# IO_Buffer.net
KiCad netlist of a schematic drawn in Altium Designer
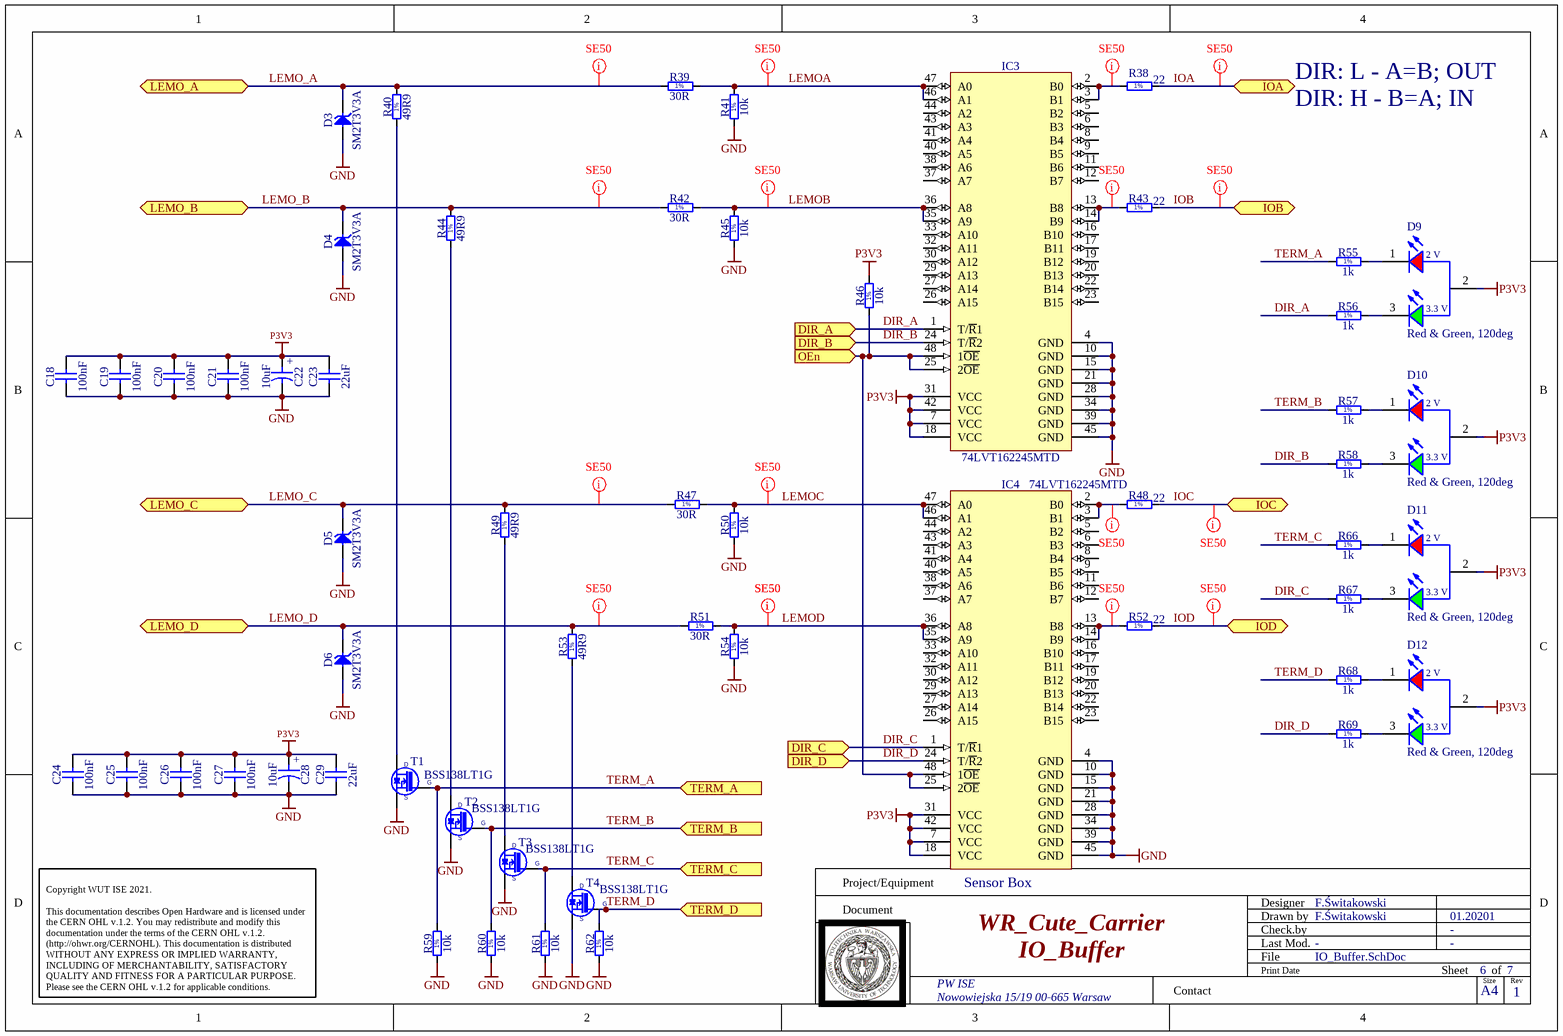
[diagram p0: IO_Buffer.SchDoc]

(export (version "E")
  (design (tool "Eeschema 10.0.6"))
  (components
    (comp (ref "C18")
      (value "100nF")
      (footprint "CAPC1005X55N")
      (description "Non-polarised capacitor")
      (fields
        (field (name "PART NUMBER") "CC0402_100NF_16V_10%_X5R")
        (field (name "VOLTAGE") "16V")
        (field (name "AUTHOR") "CERN DEM JLC")
      )
      (libsource (lib "Capacitors") (part "Capacitor - non polarized"))
    )
    (comp (ref "C19")
      (value "100nF")
      (footprint "CAPC1005X55N")
      (description "Non-polarised capacitor")
      (fields
        (field (name "PART NUMBER") "CC0402_100NF_16V_10%_X5R")
        (field (name "VOLTAGE") "16V")
        (field (name "AUTHOR") "CERN DEM JLC")
      )
      (libsource (lib "Capacitors") (part "Capacitor - non polarized"))
    )
    (comp (ref "C20")
      (value "100nF")
      (footprint "CAPC1005X55N")
      (description "Non-polarised capacitor")
      (fields
        (field (name "PART NUMBER") "CC0402_100NF_16V_10%_X5R")
        (field (name "VOLTAGE") "16V")
        (field (name "AUTHOR") "CERN DEM JLC")
      )
      (libsource (lib "Capacitors") (part "Capacitor - non polarized"))
    )
    (comp (ref "C21")
      (value "100nF")
      (footprint "CAPC1005X55N")
      (description "Non-polarised capacitor")
      (fields
        (field (name "PART NUMBER") "CC0402_100NF_16V_10%_X5R")
        (field (name "VOLTAGE") "16V")
        (field (name "AUTHOR") "CERN DEM JLC")
      )
      (libsource (lib "Capacitors") (part "Capacitor - non polarized"))
    )
    (comp (ref "C22")
      (value "10uF")
      (footprint "CAPAE430X540N")
      (description "Polarised capacitor")
      (fields
        (field (name "PART NUMBER") "CAE430-540_10UF_16V_20%")
        (field (name "VOLTAGE") "16V")
        (field (name "AUTHOR") "CERN DEM JLC")
      )
      (libsource (lib "Capacitors") (part "Capacitor - polarized"))
    )
    (comp (ref "C23")
      (value "22uF")
      (footprint "CAPC2012X135N")
      (description "Non-polarised capacitor")
      (fields
        (field (name "PART NUMBER") "CC0805_22UF_16V_10%_X5R")
        (field (name "VOLTAGE") "16V")
        (field (name "AUTHOR") "CERN DEM JLC")
      )
      (libsource (lib "Capacitors") (part "Capacitor - non polarized"))
    )
    (comp (ref "C24")
      (value "100nF")
      (footprint "CAPC1005X55N")
      (description "Non-polarised capacitor")
      (fields
        (field (name "PART NUMBER") "CC0402_100NF_16V_10%_X5R")
        (field (name "VOLTAGE") "16V")
        (field (name "AUTHOR") "CERN DEM JLC")
      )
      (libsource (lib "Capacitors") (part "Capacitor - non polarized"))
    )
    (comp (ref "C25")
      (value "100nF")
      (footprint "CAPC1005X55N")
      (description "Non-polarised capacitor")
      (fields
        (field (name "PART NUMBER") "CC0402_100NF_16V_10%_X5R")
        (field (name "VOLTAGE") "16V")
        (field (name "AUTHOR") "CERN DEM JLC")
      )
      (libsource (lib "Capacitors") (part "Capacitor - non polarized"))
    )
    (comp (ref "C26")
      (value "100nF")
      (footprint "CAPC1005X55N")
      (description "Non-polarised capacitor")
      (fields
        (field (name "PART NUMBER") "CC0402_100NF_16V_10%_X5R")
        (field (name "VOLTAGE") "16V")
        (field (name "AUTHOR") "CERN DEM JLC")
      )
      (libsource (lib "Capacitors") (part "Capacitor - non polarized"))
    )
    (comp (ref "C27")
      (value "100nF")
      (footprint "CAPC1005X55N")
      (description "Non-polarised capacitor")
      (fields
        (field (name "PART NUMBER") "CC0402_100NF_16V_10%_X5R")
        (field (name "VOLTAGE") "16V")
        (field (name "AUTHOR") "CERN DEM JLC")
      )
      (libsource (lib "Capacitors") (part "Capacitor - non polarized"))
    )
    (comp (ref "C28")
      (value "10uF")
      (footprint "CAPAE430X540N")
      (description "Polarised capacitor")
      (fields
        (field (name "PART NUMBER") "CAE430-540_10UF_16V_20%")
        (field (name "VOLTAGE") "16V")
        (field (name "AUTHOR") "CERN DEM JLC")
      )
      (libsource (lib "Capacitors") (part "Capacitor - polarized"))
    )
    (comp (ref "C29")
      (value "22uF")
      (footprint "CAPC2012X135N")
      (description "Non-polarised capacitor")
      (fields
        (field (name "PART NUMBER") "CC0805_22UF_16V_10%_X5R")
        (field (name "VOLTAGE") "16V")
        (field (name "AUTHOR") "CERN DEM JLC")
      )
      (libsource (lib "Capacitors") (part "Capacitor - non polarized"))
    )
    (comp (ref "D3")
      (value "SM2T3V3A")
      (footprint "DO-216AA")
      (description "Transient Voltage Suppressor Diode (Uni-Directional)")
      (fields
        (field (name "VOLTAGE") "3V3")
        (field (name "POWER") "200W")
        (field (name "AUTHOR") "CERN DEM BR")
      )
      (libsource (lib "ICs And Semiconductors") (part "Diode TVS Uni-Directional"))
    )
    (comp (ref "D4")
      (value "SM2T3V3A")
      (footprint "DO-216AA")
      (description "Transient Voltage Suppressor Diode (Uni-Directional)")
      (fields
        (field (name "VOLTAGE") "3V3")
        (field (name "POWER") "200W")
        (field (name "AUTHOR") "CERN DEM BR")
      )
      (libsource (lib "ICs And Semiconductors") (part "Diode TVS Uni-Directional"))
    )
    (comp (ref "D5")
      (value "SM2T3V3A")
      (footprint "DO-216AA")
      (description "Transient Voltage Suppressor Diode (Uni-Directional)")
      (fields
        (field (name "VOLTAGE") "3V3")
        (field (name "POWER") "200W")
        (field (name "AUTHOR") "CERN DEM BR")
      )
      (libsource (lib "ICs And Semiconductors") (part "Diode TVS Uni-Directional"))
    )
    (comp (ref "D6")
      (value "SM2T3V3A")
      (footprint "DO-216AA")
      (description "Transient Voltage Suppressor Diode (Uni-Directional)")
      (fields
        (field (name "VOLTAGE") "3V3")
        (field (name "POWER") "200W")
        (field (name "AUTHOR") "CERN DEM BR")
      )
      (libsource (lib "ICs And Semiconductors") (part "Diode TVS Uni-Directional"))
    )
    (comp (ref "D9")
      (value "Red & Green, 120deg")
      (footprint "WL-SBSW_1204")
      (description "WL-SBSW SMT Bi-color Side View Waterclear, size 1204, Red & Green, 120deg")
      (fields (field (name "PART NUMBER") "155124RG73200") (field (name "PUBLISHER") "Wurth Elektronik"))
      (libsource (lib "155124RG73200_Altium_WL-SBSW_rev19a") (part "155124RG73200"))
    )
    (comp (ref "D10")
      (value "Red & Green, 120deg")
      (footprint "WL-SBSW_1204")
      (description "WL-SBSW SMT Bi-color Side View Waterclear, size 1204, Red & Green, 120deg")
      (fields (field (name "PART NUMBER") "155124RG73200") (field (name "PUBLISHER") "Wurth Elektronik"))
      (libsource (lib "155124RG73200_Altium_WL-SBSW_rev19a") (part "155124RG73200"))
    )
    (comp (ref "D11")
      (value "Red & Green, 120deg")
      (footprint "WL-SBSW_1204")
      (description "WL-SBSW SMT Bi-color Side View Waterclear, size 1204, Red & Green, 120deg")
      (fields (field (name "PART NUMBER") "155124RG73200") (field (name "PUBLISHER") "Wurth Elektronik"))
      (libsource (lib "155124RG73200_Altium_WL-SBSW_rev19a") (part "155124RG73200"))
    )
    (comp (ref "D12")
      (value "Red & Green, 120deg")
      (footprint "WL-SBSW_1204")
      (description "WL-SBSW SMT Bi-color Side View Waterclear, size 1204, Red & Green, 120deg")
      (fields (field (name "PART NUMBER") "155124RG73200") (field (name "PUBLISHER") "Wurth Elektronik"))
      (libsource (lib "155124RG73200_Altium_WL-SBSW_rev19a") (part "155124RG73200"))
    )
    (comp (ref "IC3")
      (value "74LVT162245MTD")
      (footprint "SOP50P810X120-48N")
      (description "Low Voltage 16-Bit Transceiver with 3-STATE Outputs and 25 Ohm Series Resistors in A Port Outputs")
      (fields (field (name "MANUFACTURER") "FAIRCHILD SEMICONDUCTOR") (field (name "AUTHOR") "CERN DEM MR"))
      (libsource (lib "ICs And Semiconductors") (part "74162245"))
    )
    (comp (ref "IC4")
      (value "74LVT162245MTD")
      (footprint "SOP50P810X120-48N")
      (description "Low Voltage 16-Bit Transceiver with 3-STATE Outputs and 25 Ohm Series Resistors in A Port Outputs")
      (fields (field (name "MANUFACTURER") "FAIRCHILD SEMICONDUCTOR") (field (name "AUTHOR") "CERN DEM MR"))
      (libsource (lib "ICs And Semiconductors") (part "74162245"))
    )
    (comp (ref "R38")
      (value "22")
      (footprint "RESC1005X40N")
      (description "Resistor - 1%")
      (fields
        (field (name "PART NUMBER") "R0402_22R_1%_0.0625W_100PPM")
        (field (name "POWER") "0.0625W")
        (field (name "AUTHOR") "CERN DEM JLC")
      )
      (libsource (lib "Resistors") (part "Resistor - 1%"))
    )
    (comp (ref "R39")
      (value "30R")
      (footprint "RESC3225X70N")
      (description "Resistor - 5%")
      (fields
        (field (name "PART NUMBER") "R1210_30R_5%_0.5W_200ppm")
        (field (name "POWER") "0.5W")
        (field (name "AUTHOR") "CERN DEM JMW")
      )
      (libsource (lib "LIBRARY_SCH") (part "R1210_30R_5%_0.5W_200PPM"))
    )
    (comp (ref "R40")
      (value "49R9")
      (footprint "RESC3225X70N")
      (description "Resistor - 1%")
      (fields
        (field (name "PART NUMBER") "R1210_49R9_1%_0.5W_100PPM_VISHAY_CRCW")
        (field (name "POWER") "0.5W")
        (field (name "AUTHOR") "CERN DEM JMW")
      )
      (libsource (lib "Resistors") (part "Resistor - 1%"))
    )
    (comp (ref "R41")
      (value "10k")
      (footprint "RESC1005X40N")
      (description "Resistor - 1%")
      (fields
        (field (name "PART NUMBER") "R0402_10K_1%_0.0625W_100PPM")
        (field (name "POWER") "0.0625W")
        (field (name "AUTHOR") "CERN DEM JLC")
      )
      (libsource (lib "Resistors") (part "Resistor - 1%"))
    )
    (comp (ref "R42")
      (value "30R")
      (footprint "RESC3225X70N")
      (description "Resistor - 5%")
      (fields
        (field (name "PART NUMBER") "R1210_30R_5%_0.5W_200ppm")
        (field (name "POWER") "0.5W")
        (field (name "AUTHOR") "CERN DEM JMW")
      )
      (libsource (lib "LIBRARY_SCH") (part "R1210_30R_5%_0.5W_200PPM"))
    )
    (comp (ref "R43")
      (value "22")
      (footprint "RESC1005X40N")
      (description "Resistor - 1%")
      (fields
        (field (name "PART NUMBER") "R0402_22R_1%_0.0625W_100PPM")
        (field (name "POWER") "0.0625W")
        (field (name "AUTHOR") "CERN DEM JLC")
      )
      (libsource (lib "Resistors") (part "Resistor - 1%"))
    )
    (comp (ref "R44")
      (value "49R9")
      (footprint "RESC3225X70N")
      (description "Resistor - 1%")
      (fields
        (field (name "PART NUMBER") "R1210_49R9_1%_0.5W_100PPM_VISHAY_CRCW")
        (field (name "POWER") "0.5W")
        (field (name "AUTHOR") "CERN DEM JMW")
      )
      (libsource (lib "Resistors") (part "Resistor - 1%"))
    )
    (comp (ref "R45")
      (value "10k")
      (footprint "RESC1005X40N")
      (description "Resistor - 1%")
      (fields
        (field (name "PART NUMBER") "R0402_10K_1%_0.0625W_100PPM")
        (field (name "POWER") "0.0625W")
        (field (name "AUTHOR") "CERN DEM JLC")
      )
      (libsource (lib "Resistors") (part "Resistor - 1%"))
    )
    (comp (ref "R46")
      (value "10k")
      (footprint "RESC1005X40N")
      (description "Resistor - 1%")
      (fields
        (field (name "PART NUMBER") "R0402_10K_1%_0.0625W_100PPM")
        (field (name "POWER") "0.0625W")
        (field (name "AUTHOR") "CERN DEM JLC")
      )
      (libsource (lib "Resistors") (part "Resistor - 1%"))
    )
    (comp (ref "R47")
      (value "30R")
      (footprint "RESC3225X70N")
      (description "Resistor - 5%")
      (fields
        (field (name "PART NUMBER") "R1210_30R_5%_0.5W_200ppm")
        (field (name "POWER") "0.5W")
        (field (name "AUTHOR") "CERN DEM JMW")
      )
      (libsource (lib "LIBRARY_SCH") (part "R1210_30R_5%_0.5W_200PPM"))
    )
    (comp (ref "R48")
      (value "22")
      (footprint "RESC1005X40N")
      (description "Resistor - 1%")
      (fields
        (field (name "PART NUMBER") "R0402_22R_1%_0.0625W_100PPM")
        (field (name "POWER") "0.0625W")
        (field (name "AUTHOR") "CERN DEM JLC")
      )
      (libsource (lib "Resistors") (part "Resistor - 1%"))
    )
    (comp (ref "R49")
      (value "49R9")
      (footprint "RESC3225X70N")
      (description "Resistor - 1%")
      (fields
        (field (name "PART NUMBER") "R1210_49R9_1%_0.5W_100PPM_VISHAY_CRCW")
        (field (name "POWER") "0.5W")
        (field (name "AUTHOR") "CERN DEM JMW")
      )
      (libsource (lib "Resistors") (part "Resistor - 1%"))
    )
    (comp (ref "R50")
      (value "10k")
      (footprint "RESC1005X40N")
      (description "Resistor - 1%")
      (fields
        (field (name "PART NUMBER") "R0402_10K_1%_0.0625W_100PPM")
        (field (name "POWER") "0.0625W")
        (field (name "AUTHOR") "CERN DEM JLC")
      )
      (libsource (lib "Resistors") (part "Resistor - 1%"))
    )
    (comp (ref "R51")
      (value "30R")
      (footprint "RESC3225X70N")
      (description "Resistor - 5%")
      (fields
        (field (name "PART NUMBER") "R1210_30R_5%_0.5W_200ppm")
        (field (name "POWER") "0.5W")
        (field (name "AUTHOR") "CERN DEM JMW")
      )
      (libsource (lib "LIBRARY_SCH") (part "R1210_30R_5%_0.5W_200PPM"))
    )
    (comp (ref "R52")
      (value "22")
      (footprint "RESC1005X40N")
      (description "Resistor - 1%")
      (fields
        (field (name "PART NUMBER") "R0402_22R_1%_0.0625W_100PPM")
        (field (name "POWER") "0.0625W")
        (field (name "AUTHOR") "CERN DEM JLC")
      )
      (libsource (lib "Resistors") (part "Resistor - 1%"))
    )
    (comp (ref "R53")
      (value "49R9")
      (footprint "RESC3225X70N")
      (description "Resistor - 1%")
      (fields
        (field (name "PART NUMBER") "R1210_49R9_1%_0.5W_100PPM_VISHAY_CRCW")
        (field (name "POWER") "0.5W")
        (field (name "AUTHOR") "CERN DEM JMW")
      )
      (libsource (lib "Resistors") (part "Resistor - 1%"))
    )
    (comp (ref "R54")
      (value "10k")
      (footprint "RESC1005X40N")
      (description "Resistor - 1%")
      (fields
        (field (name "PART NUMBER") "R0402_10K_1%_0.0625W_100PPM")
        (field (name "POWER") "0.0625W")
        (field (name "AUTHOR") "CERN DEM JLC")
      )
      (libsource (lib "Resistors") (part "Resistor - 1%"))
    )
    (comp (ref "R55")
      (value "1k")
      (footprint "RESC1005X40N")
      (description "Resistor - 1%")
      (fields
        (field (name "PART NUMBER") "R0402_1K_1%_0.0625W_100PPM")
        (field (name "POWER") "0.0625W")
        (field (name "AUTHOR") "CERN DEM JLC")
      )
      (libsource (lib "Resistors") (part "Resistor - 1%"))
    )
    (comp (ref "R56")
      (value "1k")
      (footprint "RESC1005X40N")
      (description "Resistor - 1%")
      (fields
        (field (name "PART NUMBER") "R0402_1K_1%_0.0625W_100PPM")
        (field (name "POWER") "0.0625W")
        (field (name "AUTHOR") "CERN DEM JLC")
      )
      (libsource (lib "Resistors") (part "Resistor - 1%"))
    )
    (comp (ref "R57")
      (value "1k")
      (footprint "RESC1005X40N")
      (description "Resistor - 1%")
      (fields
        (field (name "PART NUMBER") "R0402_1K_1%_0.0625W_100PPM")
        (field (name "POWER") "0.0625W")
        (field (name "AUTHOR") "CERN DEM JLC")
      )
      (libsource (lib "Resistors") (part "Resistor - 1%"))
    )
    (comp (ref "R58")
      (value "1k")
      (footprint "RESC1005X40N")
      (description "Resistor - 1%")
      (fields
        (field (name "PART NUMBER") "R0402_1K_1%_0.0625W_100PPM")
        (field (name "POWER") "0.0625W")
        (field (name "AUTHOR") "CERN DEM JLC")
      )
      (libsource (lib "Resistors") (part "Resistor - 1%"))
    )
    (comp (ref "R59")
      (value "10k")
      (footprint "RESC1005X40N")
      (description "Resistor - 1%")
      (fields
        (field (name "PART NUMBER") "R0402_10K_1%_0.0625W_100PPM")
        (field (name "POWER") "0.0625W")
        (field (name "AUTHOR") "CERN DEM JLC")
      )
      (libsource (lib "Resistors") (part "Resistor - 1%"))
    )
    (comp (ref "R60")
      (value "10k")
      (footprint "RESC1005X40N")
      (description "Resistor - 1%")
      (fields
        (field (name "PART NUMBER") "R0402_10K_1%_0.0625W_100PPM")
        (field (name "POWER") "0.0625W")
        (field (name "AUTHOR") "CERN DEM JLC")
      )
      (libsource (lib "Resistors") (part "Resistor - 1%"))
    )
    (comp (ref "R61")
      (value "10k")
      (footprint "RESC1005X40N")
      (description "Resistor - 1%")
      (fields
        (field (name "PART NUMBER") "R0402_10K_1%_0.0625W_100PPM")
        (field (name "POWER") "0.0625W")
        (field (name "AUTHOR") "CERN DEM JLC")
      )
      (libsource (lib "Resistors") (part "Resistor - 1%"))
    )
    (comp (ref "R62")
      (value "10k")
      (footprint "RESC1005X40N")
      (description "Resistor - 1%")
      (fields
        (field (name "PART NUMBER") "R0402_10K_1%_0.0625W_100PPM")
        (field (name "POWER") "0.0625W")
        (field (name "AUTHOR") "CERN DEM JLC")
      )
      (libsource (lib "Resistors") (part "Resistor - 1%"))
    )
    (comp (ref "R66")
      (value "1k")
      (footprint "RESC1005X40N")
      (description "Resistor - 1%")
      (fields
        (field (name "PART NUMBER") "R0402_1K_1%_0.0625W_100PPM")
        (field (name "POWER") "0.0625W")
        (field (name "AUTHOR") "CERN DEM JLC")
      )
      (libsource (lib "Resistors") (part "Resistor - 1%"))
    )
    (comp (ref "R67")
      (value "1k")
      (footprint "RESC1005X40N")
      (description "Resistor - 1%")
      (fields
        (field (name "PART NUMBER") "R0402_1K_1%_0.0625W_100PPM")
        (field (name "POWER") "0.0625W")
        (field (name "AUTHOR") "CERN DEM JLC")
      )
      (libsource (lib "Resistors") (part "Resistor - 1%"))
    )
    (comp (ref "R68")
      (value "1k")
      (footprint "RESC1005X40N")
      (description "Resistor - 1%")
      (fields
        (field (name "PART NUMBER") "R0402_1K_1%_0.0625W_100PPM")
        (field (name "POWER") "0.0625W")
        (field (name "AUTHOR") "CERN DEM JLC")
      )
      (libsource (lib "Resistors") (part "Resistor - 1%"))
    )
    (comp (ref "R69")
      (value "1k")
      (footprint "RESC1005X40N")
      (description "Resistor - 1%")
      (fields
        (field (name "PART NUMBER") "R0402_1K_1%_0.0625W_100PPM")
        (field (name "POWER") "0.0625W")
        (field (name "AUTHOR") "CERN DEM JLC")
      )
      (libsource (lib "Resistors") (part "Resistor - 1%"))
    )
    (comp (ref "T1")
      (value "BSS138LT1G")
      (footprint "SOT95P240X110-3N")
      (description "N-CHANNEL MOSFET WITH DIODE")
      (fields (field (name "MANUFACTURER") "ON SEMICONDUCTOR") (field (name "AUTHOR") "CERN DEM JLC"))
      (libsource (lib "ICs And Semiconductors") (part "N-MOSFET-D 1G 2S 3D"))
    )
    (comp (ref "T2")
      (value "BSS138LT1G")
      (footprint "SOT95P240X110-3N")
      (description "N-CHANNEL MOSFET WITH DIODE")
      (fields (field (name "MANUFACTURER") "ON SEMICONDUCTOR") (field (name "AUTHOR") "CERN DEM JLC"))
      (libsource (lib "ICs And Semiconductors") (part "N-MOSFET-D 1G 2S 3D"))
    )
    (comp (ref "T3")
      (value "BSS138LT1G")
      (footprint "SOT95P240X110-3N")
      (description "N-CHANNEL MOSFET WITH DIODE")
      (fields (field (name "MANUFACTURER") "ON SEMICONDUCTOR") (field (name "AUTHOR") "CERN DEM JLC"))
      (libsource (lib "ICs And Semiconductors") (part "N-MOSFET-D 1G 2S 3D"))
    )
    (comp (ref "T4")
      (value "BSS138LT1G")
      (footprint "SOT95P240X110-3N")
      (description "N-CHANNEL MOSFET WITH DIODE")
      (fields (field (name "MANUFACTURER") "ON SEMICONDUCTOR") (field (name "AUTHOR") "CERN DEM JLC"))
      (libsource (lib "ICs And Semiconductors") (part "N-MOSFET-D 1G 2S 3D"))
    )
  )
  (nets
    (net (code "1") (name "/DIR_A") (class "Default")
      (node (ref "IC3") (pin "1") (pinfunction "T/~{R}1_1") (pintype "input"))
      (node (ref "R56") (pin "1") (pinfunction "1_1") (pintype "passive"))
    )
    (net (code "2") (name "/DIR_B") (class "Default")
      (node (ref "IC3") (pin "24") (pinfunction "T/~{R}2_24") (pintype "input"))
      (node (ref "R58") (pin "1") (pinfunction "1_1") (pintype "passive"))
    )
    (net (code "3") (name "/DIR_C") (class "Default")
      (node (ref "IC4") (pin "1") (pinfunction "T/~{R}1_1") (pintype "input"))
      (node (ref "R67") (pin "1") (pinfunction "1_1") (pintype "passive"))
    )
    (net (code "4") (name "/DIR_D") (class "Default")
      (node (ref "IC4") (pin "24") (pinfunction "T/~{R}2_24") (pintype "input"))
      (node (ref "R69") (pin "1") (pinfunction "1_1") (pintype "passive"))
    )
    (net (code "5") (name "/IOA") (class "Default")
      (node (ref "R38") (pin "2") (pinfunction "2_2") (pintype "passive"))
    )
    (net (code "6") (name "/IOB") (class "Default")
      (node (ref "R43") (pin "2") (pinfunction "2_2") (pintype "passive"))
    )
    (net (code "7") (name "/IOC") (class "Default")
      (node (ref "R48") (pin "2") (pinfunction "2_2") (pintype "passive"))
    )
    (net (code "8") (name "/IOD") (class "Default")
      (node (ref "R52") (pin "2") (pinfunction "2_2") (pintype "passive"))
    )
    (net (code "9") (name "/LEMOA") (class "Default")
      (node (ref "IC3") (pin "46") (pinfunction "A1_46") (pintype "bidirectional"))
      (node (ref "IC3") (pin "47") (pinfunction "A0_47") (pintype "bidirectional"))
      (node (ref "R39") (pin "2") (pinfunction "2_2") (pintype "passive"))
      (node (ref "R41") (pin "2") (pinfunction "2_2") (pintype "passive"))
    )
    (net (code "10") (name "/LEMOB") (class "Default")
      (node (ref "IC3") (pin "35") (pinfunction "A9_35") (pintype "bidirectional"))
      (node (ref "IC3") (pin "36") (pinfunction "A8_36") (pintype "bidirectional"))
      (node (ref "R42") (pin "2") (pinfunction "2_2") (pintype "passive"))
      (node (ref "R45") (pin "2") (pinfunction "2_2") (pintype "passive"))
    )
    (net (code "11") (name "/LEMOC") (class "Default")
      (node (ref "IC4") (pin "46") (pinfunction "A1_46") (pintype "bidirectional"))
      (node (ref "IC4") (pin "47") (pinfunction "A0_47") (pintype "bidirectional"))
      (node (ref "R47") (pin "2") (pinfunction "2_2") (pintype "passive"))
      (node (ref "R50") (pin "2") (pinfunction "2_2") (pintype "passive"))
    )
    (net (code "12") (name "/LEMOD") (class "Default")
      (node (ref "IC4") (pin "35") (pinfunction "A9_35") (pintype "bidirectional"))
      (node (ref "IC4") (pin "36") (pinfunction "A8_36") (pintype "bidirectional"))
      (node (ref "R51") (pin "2") (pinfunction "2_2") (pintype "passive"))
      (node (ref "R54") (pin "2") (pinfunction "2_2") (pintype "passive"))
    )
    (net (code "13") (name "/LEMO_A") (class "Default")
      (node (ref "D3") (pin "1") (pinfunction "C_1") (pintype "passive"))
      (node (ref "R39") (pin "1") (pinfunction "1_1") (pintype "passive"))
      (node (ref "R40") (pin "2") (pinfunction "2_2") (pintype "passive"))
    )
    (net (code "14") (name "/LEMO_B") (class "Default")
      (node (ref "D4") (pin "1") (pinfunction "C_1") (pintype "passive"))
      (node (ref "R42") (pin "1") (pinfunction "1_1") (pintype "passive"))
      (node (ref "R44") (pin "2") (pinfunction "2_2") (pintype "passive"))
    )
    (net (code "15") (name "/LEMO_C") (class "Default")
      (node (ref "D5") (pin "1") (pinfunction "C_1") (pintype "passive"))
      (node (ref "R47") (pin "1") (pinfunction "1_1") (pintype "passive"))
      (node (ref "R49") (pin "2") (pinfunction "2_2") (pintype "passive"))
    )
    (net (code "16") (name "/LEMO_D") (class "Default")
      (node (ref "D6") (pin "1") (pinfunction "C_1") (pintype "passive"))
      (node (ref "R51") (pin "1") (pinfunction "1_1") (pintype "passive"))
      (node (ref "R53") (pin "2") (pinfunction "2_2") (pintype "passive"))
    )
    (net (code "17") (name "/OEn") (class "Default")
      (node (ref "IC3") (pin "25") (pinfunction "2~{OE}_25") (pintype "input"))
      (node (ref "IC3") (pin "48") (pinfunction "1~{OE}_48") (pintype "input"))
      (node (ref "IC4") (pin "25") (pinfunction "2~{OE}_25") (pintype "input"))
      (node (ref "IC4") (pin "48") (pinfunction "1~{OE}_48") (pintype "input"))
      (node (ref "R46") (pin "1") (pinfunction "1_1") (pintype "passive"))
    )
    (net (code "18") (name "/TERM_A") (class "Default")
      (node (ref "R55") (pin "1") (pinfunction "1_1") (pintype "passive"))
      (node (ref "R59") (pin "2") (pinfunction "2_2") (pintype "passive"))
      (node (ref "T1") (pin "1") (pinfunction "G_1") (pintype "passive"))
    )
    (net (code "19") (name "/TERM_B") (class "Default")
      (node (ref "R57") (pin "1") (pinfunction "1_1") (pintype "passive"))
      (node (ref "R60") (pin "2") (pinfunction "2_2") (pintype "passive"))
      (node (ref "T2") (pin "1") (pinfunction "G_1") (pintype "passive"))
    )
    (net (code "20") (name "/TERM_C") (class "Default")
      (node (ref "R61") (pin "2") (pinfunction "2_2") (pintype "passive"))
      (node (ref "R66") (pin "1") (pinfunction "1_1") (pintype "passive"))
      (node (ref "T3") (pin "1") (pinfunction "G_1") (pintype "passive"))
    )
    (net (code "21") (name "/TERM_D") (class "Default")
      (node (ref "R62") (pin "2") (pinfunction "2_2") (pintype "passive"))
      (node (ref "R68") (pin "1") (pinfunction "1_1") (pintype "passive"))
      (node (ref "T4") (pin "1") (pinfunction "G_1") (pintype "passive"))
    )
    (net (code "22") (name "GND") (class "Default")
      (node (ref "C18") (pin "1") (pinfunction "1_1") (pintype "passive"))
      (node (ref "C19") (pin "1") (pinfunction "1_1") (pintype "passive"))
      (node (ref "C20") (pin "1") (pinfunction "1_1") (pintype "passive"))
      (node (ref "C21") (pin "1") (pinfunction "1_1") (pintype "passive"))
      (node (ref "C22") (pin "2") (pinfunction "2_2") (pintype "passive"))
      (node (ref "C23") (pin "1") (pinfunction "1_1") (pintype "passive"))
      (node (ref "C24") (pin "1") (pinfunction "1_1") (pintype "passive"))
      (node (ref "C25") (pin "1") (pinfunction "1_1") (pintype "passive"))
      (node (ref "C26") (pin "1") (pinfunction "1_1") (pintype "passive"))
      (node (ref "C27") (pin "1") (pinfunction "1_1") (pintype "passive"))
      (node (ref "C28") (pin "2") (pinfunction "2_2") (pintype "passive"))
      (node (ref "C29") (pin "1") (pinfunction "1_1") (pintype "passive"))
      (node (ref "D3") (pin "2") (pinfunction "A_2") (pintype "passive"))
      (node (ref "D4") (pin "2") (pinfunction "A_2") (pintype "passive"))
      (node (ref "D5") (pin "2") (pinfunction "A_2") (pintype "passive"))
      (node (ref "D6") (pin "2") (pinfunction "A_2") (pintype "passive"))
      (node (ref "IC3") (pin "10") (pinfunction "GND_10") (pintype "power_in"))
      (node (ref "IC3") (pin "15") (pinfunction "GND_15") (pintype "power_in"))
      (node (ref "IC3") (pin "21") (pinfunction "GND_21") (pintype "power_in"))
      (node (ref "IC3") (pin "28") (pinfunction "GND_28") (pintype "power_in"))
      (node (ref "IC3") (pin "34") (pinfunction "GND_34") (pintype "power_in"))
      (node (ref "IC3") (pin "39") (pinfunction "GND_39") (pintype "power_in"))
      (node (ref "IC3") (pin "4") (pinfunction "GND_4") (pintype "power_in"))
      (node (ref "IC3") (pin "45") (pinfunction "GND_45") (pintype "power_in"))
      (node (ref "IC4") (pin "10") (pinfunction "GND_10") (pintype "power_in"))
      (node (ref "IC4") (pin "15") (pinfunction "GND_15") (pintype "power_in"))
      (node (ref "IC4") (pin "21") (pinfunction "GND_21") (pintype "power_in"))
      (node (ref "IC4") (pin "28") (pinfunction "GND_28") (pintype "power_in"))
      (node (ref "IC4") (pin "34") (pinfunction "GND_34") (pintype "power_in"))
      (node (ref "IC4") (pin "39") (pinfunction "GND_39") (pintype "power_in"))
      (node (ref "IC4") (pin "4") (pinfunction "GND_4") (pintype "power_in"))
      (node (ref "IC4") (pin "45") (pinfunction "GND_45") (pintype "power_in"))
      (node (ref "R41") (pin "1") (pinfunction "1_1") (pintype "passive"))
      (node (ref "R45") (pin "1") (pinfunction "1_1") (pintype "passive"))
      (node (ref "R50") (pin "1") (pinfunction "1_1") (pintype "passive"))
      (node (ref "R54") (pin "1") (pinfunction "1_1") (pintype "passive"))
      (node (ref "R59") (pin "1") (pinfunction "1_1") (pintype "passive"))
      (node (ref "R60") (pin "1") (pinfunction "1_1") (pintype "passive"))
      (node (ref "R61") (pin "1") (pinfunction "1_1") (pintype "passive"))
      (node (ref "R62") (pin "1") (pinfunction "1_1") (pintype "passive"))
      (node (ref "T1") (pin "2") (pinfunction "S_2") (pintype "passive"))
      (node (ref "T2") (pin "2") (pinfunction "S_2") (pintype "passive"))
      (node (ref "T3") (pin "2") (pinfunction "S_2") (pintype "passive"))
      (node (ref "T4") (pin "2") (pinfunction "S_2") (pintype "passive"))
    )
    (net (code "23") (name "Net-(D9-K-Pad1)") (class "Default")
      (node (ref "D9") (pin "1") (pinfunction "K_1") (pintype "passive"))
      (node (ref "R55") (pin "2") (pinfunction "2_2") (pintype "passive"))
    )
    (net (code "24") (name "Net-(D9-K-Pad3)") (class "Default")
      (node (ref "D9") (pin "3") (pinfunction "K_3") (pintype "passive"))
      (node (ref "R56") (pin "2") (pinfunction "2_2") (pintype "passive"))
    )
    (net (code "25") (name "Net-(D10-K-Pad1)") (class "Default")
      (node (ref "D10") (pin "1") (pinfunction "K_1") (pintype "passive"))
      (node (ref "R57") (pin "2") (pinfunction "2_2") (pintype "passive"))
    )
    (net (code "26") (name "Net-(D10-K-Pad3)") (class "Default")
      (node (ref "D10") (pin "3") (pinfunction "K_3") (pintype "passive"))
      (node (ref "R58") (pin "2") (pinfunction "2_2") (pintype "passive"))
    )
    (net (code "27") (name "Net-(D11-K-Pad1)") (class "Default")
      (node (ref "D11") (pin "1") (pinfunction "K_1") (pintype "passive"))
      (node (ref "R66") (pin "2") (pinfunction "2_2") (pintype "passive"))
    )
    (net (code "28") (name "Net-(D11-K-Pad3)") (class "Default")
      (node (ref "D11") (pin "3") (pinfunction "K_3") (pintype "passive"))
      (node (ref "R67") (pin "2") (pinfunction "2_2") (pintype "passive"))
    )
    (net (code "29") (name "Net-(D12-K-Pad1)") (class "Default")
      (node (ref "D12") (pin "1") (pinfunction "K_1") (pintype "passive"))
      (node (ref "R68") (pin "2") (pinfunction "2_2") (pintype "passive"))
    )
    (net (code "30") (name "Net-(D12-K-Pad3)") (class "Default")
      (node (ref "D12") (pin "3") (pinfunction "K_3") (pintype "passive"))
      (node (ref "R69") (pin "2") (pinfunction "2_2") (pintype "passive"))
    )
    (net (code "31") (name "Net-(IC3-B0)") (class "Default")
      (node (ref "IC3") (pin "2") (pinfunction "B0_2") (pintype "bidirectional"))
      (node (ref "IC3") (pin "3") (pinfunction "B1_3") (pintype "bidirectional"))
      (node (ref "R38") (pin "1") (pinfunction "1_1") (pintype "passive"))
    )
    (net (code "32") (name "Net-(IC3-B8)") (class "Default")
      (node (ref "IC3") (pin "13") (pinfunction "B8_13") (pintype "bidirectional"))
      (node (ref "IC3") (pin "14") (pinfunction "B9_14") (pintype "bidirectional"))
      (node (ref "R43") (pin "1") (pinfunction "1_1") (pintype "passive"))
    )
    (net (code "33") (name "Net-(IC4-B0)") (class "Default")
      (node (ref "IC4") (pin "2") (pinfunction "B0_2") (pintype "bidirectional"))
      (node (ref "IC4") (pin "3") (pinfunction "B1_3") (pintype "bidirectional"))
      (node (ref "R48") (pin "1") (pinfunction "1_1") (pintype "passive"))
    )
    (net (code "34") (name "Net-(IC4-B8)") (class "Default")
      (node (ref "IC4") (pin "13") (pinfunction "B8_13") (pintype "bidirectional"))
      (node (ref "IC4") (pin "14") (pinfunction "B9_14") (pintype "bidirectional"))
      (node (ref "R52") (pin "1") (pinfunction "1_1") (pintype "passive"))
    )
    (net (code "35") (name "Net-(T1-D)") (class "Default")
      (node (ref "R40") (pin "1") (pinfunction "1_1") (pintype "passive"))
      (node (ref "T1") (pin "3") (pinfunction "D_3") (pintype "passive"))
    )
    (net (code "36") (name "Net-(T2-D)") (class "Default")
      (node (ref "R44") (pin "1") (pinfunction "1_1") (pintype "passive"))
      (node (ref "T2") (pin "3") (pinfunction "D_3") (pintype "passive"))
    )
    (net (code "37") (name "Net-(T3-D)") (class "Default")
      (node (ref "R49") (pin "1") (pinfunction "1_1") (pintype "passive"))
      (node (ref "T3") (pin "3") (pinfunction "D_3") (pintype "passive"))
    )
    (net (code "38") (name "Net-(T4-D)") (class "Default")
      (node (ref "R53") (pin "1") (pinfunction "1_1") (pintype "passive"))
      (node (ref "T4") (pin "3") (pinfunction "D_3") (pintype "passive"))
    )
    (net (code "39") (name "P3V3") (class "Default")
      (node (ref "C18") (pin "2") (pinfunction "2_2") (pintype "passive"))
      (node (ref "C19") (pin "2") (pinfunction "2_2") (pintype "passive"))
      (node (ref "C20") (pin "2") (pinfunction "2_2") (pintype "passive"))
      (node (ref "C21") (pin "2") (pinfunction "2_2") (pintype "passive"))
      (node (ref "C22") (pin "1") (pinfunction "1_1") (pintype "passive"))
      (node (ref "C23") (pin "2") (pinfunction "2_2") (pintype "passive"))
      (node (ref "C24") (pin "2") (pinfunction "2_2") (pintype "passive"))
      (node (ref "C25") (pin "2") (pinfunction "2_2") (pintype "passive"))
      (node (ref "C26") (pin "2") (pinfunction "2_2") (pintype "passive"))
      (node (ref "C27") (pin "2") (pinfunction "2_2") (pintype "passive"))
      (node (ref "C28") (pin "1") (pinfunction "1_1") (pintype "passive"))
      (node (ref "C29") (pin "2") (pinfunction "2_2") (pintype "passive"))
      (node (ref "D10") (pin "2") (pinfunction "A_2") (pintype "passive"))
      (node (ref "D11") (pin "2") (pinfunction "A_2") (pintype "passive"))
      (node (ref "D12") (pin "2") (pinfunction "A_2") (pintype "passive"))
      (node (ref "D9") (pin "2") (pinfunction "A_2") (pintype "passive"))
      (node (ref "IC3") (pin "18") (pinfunction "VCC_18") (pintype "power_in"))
      (node (ref "IC3") (pin "31") (pinfunction "VCC_31") (pintype "power_in"))
      (node (ref "IC3") (pin "42") (pinfunction "VCC_42") (pintype "power_in"))
      (node (ref "IC3") (pin "7") (pinfunction "VCC_7") (pintype "power_in"))
      (node (ref "IC4") (pin "18") (pinfunction "VCC_18") (pintype "power_in"))
      (node (ref "IC4") (pin "31") (pinfunction "VCC_31") (pintype "power_in"))
      (node (ref "IC4") (pin "42") (pinfunction "VCC_42") (pintype "power_in"))
      (node (ref "IC4") (pin "7") (pinfunction "VCC_7") (pintype "power_in"))
      (node (ref "R46") (pin "2") (pinfunction "2_2") (pintype "passive"))
    )
    (net (code "40") (name "unconnected-(IC3-A2-Pad44)") (class "Default")
      (node (ref "IC3") (pin "44") (pinfunction "A2_44") (pintype "bidirectional"))
    )
    (net (code "41") (name "unconnected-(IC3-A3-Pad43)") (class "Default")
      (node (ref "IC3") (pin "43") (pinfunction "A3_43") (pintype "bidirectional"))
    )
    (net (code "42") (name "unconnected-(IC3-A4-Pad41)") (class "Default")
      (node (ref "IC3") (pin "41") (pinfunction "A4_41") (pintype "bidirectional"))
    )
    (net (code "43") (name "unconnected-(IC3-A5-Pad40)") (class "Default")
      (node (ref "IC3") (pin "40") (pinfunction "A5_40") (pintype "bidirectional"))
    )
    (net (code "44") (name "unconnected-(IC3-A6-Pad38)") (class "Default")
      (node (ref "IC3") (pin "38") (pinfunction "A6_38") (pintype "bidirectional"))
    )
    (net (code "45") (name "unconnected-(IC3-A7-Pad37)") (class "Default")
      (node (ref "IC3") (pin "37") (pinfunction "A7_37") (pintype "bidirectional"))
    )
    (net (code "46") (name "unconnected-(IC3-A10-Pad33)") (class "Default")
      (node (ref "IC3") (pin "33") (pinfunction "A10_33") (pintype "bidirectional"))
    )
    (net (code "47") (name "unconnected-(IC3-A11-Pad32)") (class "Default")
      (node (ref "IC3") (pin "32") (pinfunction "A11_32") (pintype "bidirectional"))
    )
    (net (code "48") (name "unconnected-(IC3-A12-Pad30)") (class "Default")
      (node (ref "IC3") (pin "30") (pinfunction "A12_30") (pintype "bidirectional"))
    )
    (net (code "49") (name "unconnected-(IC3-A13-Pad29)") (class "Default")
      (node (ref "IC3") (pin "29") (pinfunction "A13_29") (pintype "bidirectional"))
    )
    (net (code "50") (name "unconnected-(IC3-A14-Pad27)") (class "Default")
      (node (ref "IC3") (pin "27") (pinfunction "A14_27") (pintype "bidirectional"))
    )
    (net (code "51") (name "unconnected-(IC3-A15-Pad26)") (class "Default")
      (node (ref "IC3") (pin "26") (pinfunction "A15_26") (pintype "bidirectional"))
    )
    (net (code "52") (name "unconnected-(IC3-B2-Pad5)") (class "Default")
      (node (ref "IC3") (pin "5") (pinfunction "B2_5") (pintype "bidirectional"))
    )
    (net (code "53") (name "unconnected-(IC3-B3-Pad6)") (class "Default")
      (node (ref "IC3") (pin "6") (pinfunction "B3_6") (pintype "bidirectional"))
    )
    (net (code "54") (name "unconnected-(IC3-B4-Pad8)") (class "Default")
      (node (ref "IC3") (pin "8") (pinfunction "B4_8") (pintype "bidirectional"))
    )
    (net (code "55") (name "unconnected-(IC3-B5-Pad9)") (class "Default")
      (node (ref "IC3") (pin "9") (pinfunction "B5_9") (pintype "bidirectional"))
    )
    (net (code "56") (name "unconnected-(IC3-B6-Pad11)") (class "Default")
      (node (ref "IC3") (pin "11") (pinfunction "B6_11") (pintype "bidirectional"))
    )
    (net (code "57") (name "unconnected-(IC3-B7-Pad12)") (class "Default")
      (node (ref "IC3") (pin "12") (pinfunction "B7_12") (pintype "bidirectional"))
    )
    (net (code "58") (name "unconnected-(IC3-B10-Pad16)") (class "Default")
      (node (ref "IC3") (pin "16") (pinfunction "B10_16") (pintype "bidirectional"))
    )
    (net (code "59") (name "unconnected-(IC3-B11-Pad17)") (class "Default")
      (node (ref "IC3") (pin "17") (pinfunction "B11_17") (pintype "bidirectional"))
    )
    (net (code "60") (name "unconnected-(IC3-B12-Pad19)") (class "Default")
      (node (ref "IC3") (pin "19") (pinfunction "B12_19") (pintype "bidirectional"))
    )
    (net (code "61") (name "unconnected-(IC3-B13-Pad20)") (class "Default")
      (node (ref "IC3") (pin "20") (pinfunction "B13_20") (pintype "bidirectional"))
    )
    (net (code "62") (name "unconnected-(IC3-B14-Pad22)") (class "Default")
      (node (ref "IC3") (pin "22") (pinfunction "B14_22") (pintype "bidirectional"))
    )
    (net (code "63") (name "unconnected-(IC3-B15-Pad23)") (class "Default")
      (node (ref "IC3") (pin "23") (pinfunction "B15_23") (pintype "bidirectional"))
    )
    (net (code "64") (name "unconnected-(IC4-A2-Pad44)") (class "Default")
      (node (ref "IC4") (pin "44") (pinfunction "A2_44") (pintype "bidirectional"))
    )
    (net (code "65") (name "unconnected-(IC4-A3-Pad43)") (class "Default")
      (node (ref "IC4") (pin "43") (pinfunction "A3_43") (pintype "bidirectional"))
    )
    (net (code "66") (name "unconnected-(IC4-A4-Pad41)") (class "Default")
      (node (ref "IC4") (pin "41") (pinfunction "A4_41") (pintype "bidirectional"))
    )
    (net (code "67") (name "unconnected-(IC4-A5-Pad40)") (class "Default")
      (node (ref "IC4") (pin "40") (pinfunction "A5_40") (pintype "bidirectional"))
    )
    (net (code "68") (name "unconnected-(IC4-A6-Pad38)") (class "Default")
      (node (ref "IC4") (pin "38") (pinfunction "A6_38") (pintype "bidirectional"))
    )
    (net (code "69") (name "unconnected-(IC4-A7-Pad37)") (class "Default")
      (node (ref "IC4") (pin "37") (pinfunction "A7_37") (pintype "bidirectional"))
    )
    (net (code "70") (name "unconnected-(IC4-A10-Pad33)") (class "Default")
      (node (ref "IC4") (pin "33") (pinfunction "A10_33") (pintype "bidirectional"))
    )
    (net (code "71") (name "unconnected-(IC4-A11-Pad32)") (class "Default")
      (node (ref "IC4") (pin "32") (pinfunction "A11_32") (pintype "bidirectional"))
    )
    (net (code "72") (name "unconnected-(IC4-A12-Pad30)") (class "Default")
      (node (ref "IC4") (pin "30") (pinfunction "A12_30") (pintype "bidirectional"))
    )
    (net (code "73") (name "unconnected-(IC4-A13-Pad29)") (class "Default")
      (node (ref "IC4") (pin "29") (pinfunction "A13_29") (pintype "bidirectional"))
    )
    (net (code "74") (name "unconnected-(IC4-A14-Pad27)") (class "Default")
      (node (ref "IC4") (pin "27") (pinfunction "A14_27") (pintype "bidirectional"))
    )
    (net (code "75") (name "unconnected-(IC4-A15-Pad26)") (class "Default")
      (node (ref "IC4") (pin "26") (pinfunction "A15_26") (pintype "bidirectional"))
    )
    (net (code "76") (name "unconnected-(IC4-B2-Pad5)") (class "Default")
      (node (ref "IC4") (pin "5") (pinfunction "B2_5") (pintype "bidirectional"))
    )
    (net (code "77") (name "unconnected-(IC4-B3-Pad6)") (class "Default")
      (node (ref "IC4") (pin "6") (pinfunction "B3_6") (pintype "bidirectional"))
    )
    (net (code "78") (name "unconnected-(IC4-B4-Pad8)") (class "Default")
      (node (ref "IC4") (pin "8") (pinfunction "B4_8") (pintype "bidirectional"))
    )
    (net (code "79") (name "unconnected-(IC4-B5-Pad9)") (class "Default")
      (node (ref "IC4") (pin "9") (pinfunction "B5_9") (pintype "bidirectional"))
    )
    (net (code "80") (name "unconnected-(IC4-B6-Pad11)") (class "Default")
      (node (ref "IC4") (pin "11") (pinfunction "B6_11") (pintype "bidirectional"))
    )
    (net (code "81") (name "unconnected-(IC4-B7-Pad12)") (class "Default")
      (node (ref "IC4") (pin "12") (pinfunction "B7_12") (pintype "bidirectional"))
    )
    (net (code "82") (name "unconnected-(IC4-B10-Pad16)") (class "Default")
      (node (ref "IC4") (pin "16") (pinfunction "B10_16") (pintype "bidirectional"))
    )
    (net (code "83") (name "unconnected-(IC4-B11-Pad17)") (class "Default")
      (node (ref "IC4") (pin "17") (pinfunction "B11_17") (pintype "bidirectional"))
    )
    (net (code "84") (name "unconnected-(IC4-B12-Pad19)") (class "Default")
      (node (ref "IC4") (pin "19") (pinfunction "B12_19") (pintype "bidirectional"))
    )
    (net (code "85") (name "unconnected-(IC4-B13-Pad20)") (class "Default")
      (node (ref "IC4") (pin "20") (pinfunction "B13_20") (pintype "bidirectional"))
    )
    (net (code "86") (name "unconnected-(IC4-B14-Pad22)") (class "Default")
      (node (ref "IC4") (pin "22") (pinfunction "B14_22") (pintype "bidirectional"))
    )
    (net (code "87") (name "unconnected-(IC4-B15-Pad23)") (class "Default")
      (node (ref "IC4") (pin "23") (pinfunction "B15_23") (pintype "bidirectional"))
    )
  )
)
